# BMS.net
KiCad netlist of a schematic drawn in EAGLE
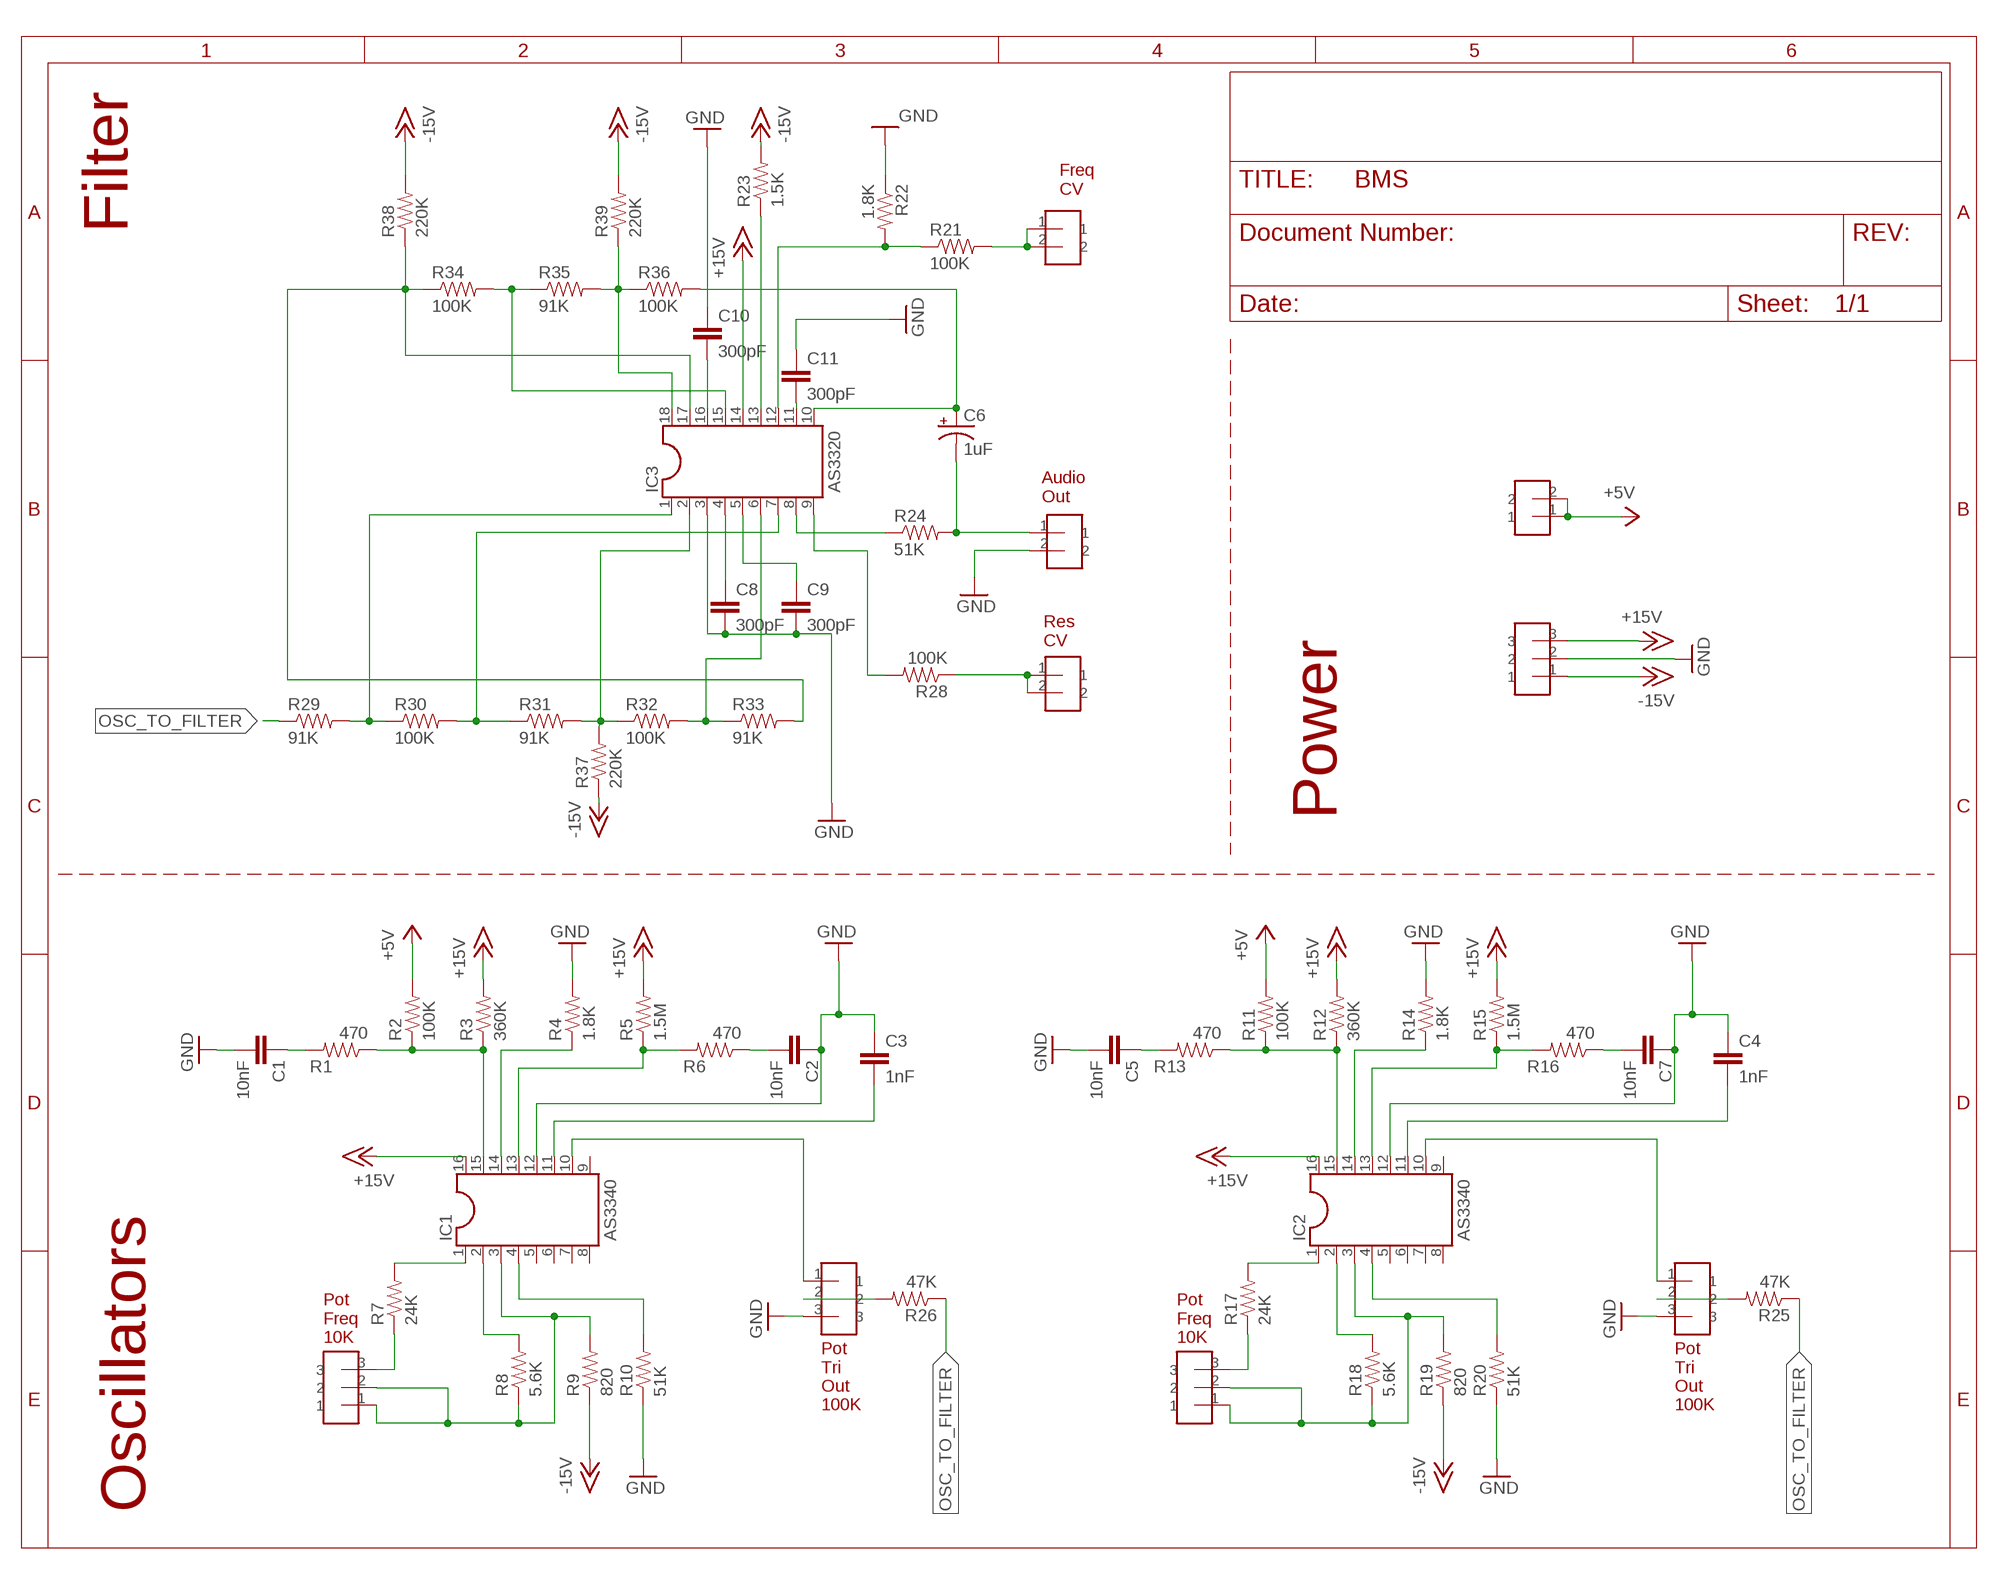
[diagram p0: schematic, sheet 1]

(export (version "E")
  (design (tool "Eeschema 10.0.6"))
  (components
    (comp (ref "C1")
      (value "10nF")
      (footprint "eagle-import:0805")
      (libsource (lib "eagle-import") (part "COMPONENT_CAP-0805"))
    )
    (comp (ref "C2")
      (value "10nF")
      (footprint "eagle-import:0805")
      (libsource (lib "eagle-import") (part "COMPONENT_CAP-0805"))
    )
    (comp (ref "C3")
      (value "1nF")
      (footprint "eagle-import:0805")
      (libsource (lib "eagle-import") (part "COMPONENT_CAP-0805"))
    )
    (comp (ref "C4")
      (value "1nF")
      (footprint "eagle-import:0805")
      (libsource (lib "eagle-import") (part "COMPONENT_CAP-0805"))
    )
    (comp (ref "C5")
      (value "10nF")
      (footprint "eagle-import:0805")
      (libsource (lib "eagle-import") (part "COMPONENT_CAP-0805"))
    )
    (comp (ref "C6")
      (value "1uF")
      (footprint "eagle-import:CAP_RADIAL_CAN_10MM")
      (libsource (lib "eagle-import") (part "COMPONENT_CAP_POL-6.3MM"))
    )
    (comp (ref "C7")
      (value "10nF")
      (footprint "eagle-import:0805")
      (libsource (lib "eagle-import") (part "COMPONENT_CAP-0805"))
    )
    (comp (ref "C8")
      (value "300pF")
      (footprint "eagle-import:0805")
      (libsource (lib "eagle-import") (part "COMPONENT_CAP-0805"))
    )
    (comp (ref "C9")
      (value "300pF")
      (footprint "eagle-import:0805")
      (libsource (lib "eagle-import") (part "COMPONENT_CAP-0805"))
    )
    (comp (ref "C10")
      (value "300pF")
      (footprint "eagle-import:0805")
      (libsource (lib "eagle-import") (part "COMPONENT_CAP-0805"))
    )
    (comp (ref "C11")
      (value "300pF")
      (footprint "eagle-import:0805")
      (libsource (lib "eagle-import") (part "COMPONENT_CAP-0805"))
    )
    (comp (ref "IC1")
      (value "AS3340")
      (footprint "eagle-import:SOCKET-16")
      (libsource (lib "eagle-import") (part "DIL16S"))
    )
    (comp (ref "IC2")
      (value "AS3340")
      (footprint "eagle-import:SOCKET-16")
      (libsource (lib "eagle-import") (part "DIL16S"))
    )
    (comp (ref "IC3")
      (value "AS3320")
      (footprint "eagle-import:SOCKET-18")
      (libsource (lib "eagle-import") (part "DIL18S"))
    )
    (comp (ref "R1")
      (value "470")
      (footprint "eagle-import:0805")
      (libsource (lib "eagle-import") (part "COMPONENT_RESISTOR-0805"))
    )
    (comp (ref "R2")
      (value "100K")
      (footprint "eagle-import:0805")
      (libsource (lib "eagle-import") (part "COMPONENT_RESISTOR-0805"))
    )
    (comp (ref "R3")
      (value "360K")
      (footprint "eagle-import:0805")
      (libsource (lib "eagle-import") (part "COMPONENT_RESISTOR-0805"))
    )
    (comp (ref "R4")
      (value "1.8K")
      (footprint "eagle-import:0805")
      (libsource (lib "eagle-import") (part "COMPONENT_RESISTOR-0805"))
    )
    (comp (ref "R5")
      (value "1.5M")
      (footprint "eagle-import:0805")
      (libsource (lib "eagle-import") (part "COMPONENT_RESISTOR-0805"))
    )
    (comp (ref "R6")
      (value "470")
      (footprint "eagle-import:0805")
      (libsource (lib "eagle-import") (part "COMPONENT_RESISTOR-0805"))
    )
    (comp (ref "R7")
      (value "24K")
      (footprint "eagle-import:0805")
      (libsource (lib "eagle-import") (part "COMPONENT_RESISTOR-0805"))
    )
    (comp (ref "R8")
      (value "5.6K")
      (footprint "eagle-import:0805")
      (libsource (lib "eagle-import") (part "COMPONENT_RESISTOR-0805"))
    )
    (comp (ref "R9")
      (value "820")
      (footprint "eagle-import:0805")
      (libsource (lib "eagle-import") (part "COMPONENT_RESISTOR-0805"))
    )
    (comp (ref "R10")
      (value "51K")
      (footprint "eagle-import:0805")
      (libsource (lib "eagle-import") (part "COMPONENT_RESISTOR-0805"))
    )
    (comp (ref "R11")
      (value "100K")
      (footprint "eagle-import:0805")
      (libsource (lib "eagle-import") (part "COMPONENT_RESISTOR-0805"))
    )
    (comp (ref "R12")
      (value "360K")
      (footprint "eagle-import:0805")
      (libsource (lib "eagle-import") (part "COMPONENT_RESISTOR-0805"))
    )
    (comp (ref "R13")
      (value "470")
      (footprint "eagle-import:0805")
      (libsource (lib "eagle-import") (part "COMPONENT_RESISTOR-0805"))
    )
    (comp (ref "R14")
      (value "1.8K")
      (footprint "eagle-import:0805")
      (libsource (lib "eagle-import") (part "COMPONENT_RESISTOR-0805"))
    )
    (comp (ref "R15")
      (value "1.5M")
      (footprint "eagle-import:0805")
      (libsource (lib "eagle-import") (part "COMPONENT_RESISTOR-0805"))
    )
    (comp (ref "R16")
      (value "470")
      (footprint "eagle-import:0805")
      (libsource (lib "eagle-import") (part "COMPONENT_RESISTOR-0805"))
    )
    (comp (ref "R17")
      (value "24K")
      (footprint "eagle-import:0805")
      (libsource (lib "eagle-import") (part "COMPONENT_RESISTOR-0805"))
    )
    (comp (ref "R18")
      (value "5.6K")
      (footprint "eagle-import:0805")
      (libsource (lib "eagle-import") (part "COMPONENT_RESISTOR-0805"))
    )
    (comp (ref "R19")
      (value "820")
      (footprint "eagle-import:0805")
      (libsource (lib "eagle-import") (part "COMPONENT_RESISTOR-0805"))
    )
    (comp (ref "R20")
      (value "51K")
      (footprint "eagle-import:0805")
      (libsource (lib "eagle-import") (part "COMPONENT_RESISTOR-0805"))
    )
    (comp (ref "R21")
      (value "100K")
      (footprint "eagle-import:0805")
      (libsource (lib "eagle-import") (part "COMPONENT_RESISTOR-0805"))
    )
    (comp (ref "R22")
      (value "1.8K")
      (footprint "eagle-import:0805")
      (libsource (lib "eagle-import") (part "COMPONENT_RESISTOR-0805"))
    )
    (comp (ref "R23")
      (value "1.5K")
      (footprint "eagle-import:0805")
      (libsource (lib "eagle-import") (part "COMPONENT_RESISTOR-0805"))
    )
    (comp (ref "R24")
      (value "51K")
      (footprint "eagle-import:0805")
      (libsource (lib "eagle-import") (part "COMPONENT_RESISTOR-0805"))
    )
    (comp (ref "R25")
      (value "47K")
      (footprint "eagle-import:0805")
      (libsource (lib "eagle-import") (part "COMPONENT_RESISTOR-0805"))
    )
    (comp (ref "R26")
      (value "47K")
      (footprint "eagle-import:0805")
      (libsource (lib "eagle-import") (part "COMPONENT_RESISTOR-0805"))
    )
    (comp (ref "R28")
      (value "100K")
      (footprint "eagle-import:0805")
      (libsource (lib "eagle-import") (part "COMPONENT_RESISTOR-0805"))
    )
    (comp (ref "R29")
      (value "91K")
      (footprint "eagle-import:0805")
      (libsource (lib "eagle-import") (part "COMPONENT_RESISTOR-0805"))
    )
    (comp (ref "R30")
      (value "100K")
      (footprint "eagle-import:0805")
      (libsource (lib "eagle-import") (part "COMPONENT_RESISTOR-0805"))
    )
    (comp (ref "R31")
      (value "91K")
      (footprint "eagle-import:0805")
      (libsource (lib "eagle-import") (part "COMPONENT_RESISTOR-0805"))
    )
    (comp (ref "R32")
      (value "100K")
      (footprint "eagle-import:0805")
      (libsource (lib "eagle-import") (part "COMPONENT_RESISTOR-0805"))
    )
    (comp (ref "R33")
      (value "91K")
      (footprint "eagle-import:0805")
      (libsource (lib "eagle-import") (part "COMPONENT_RESISTOR-0805"))
    )
    (comp (ref "R34")
      (value "100K")
      (footprint "eagle-import:0805")
      (libsource (lib "eagle-import") (part "COMPONENT_RESISTOR-0805"))
    )
    (comp (ref "R35")
      (value "91K")
      (footprint "eagle-import:0805")
      (libsource (lib "eagle-import") (part "COMPONENT_RESISTOR-0805"))
    )
    (comp (ref "R36")
      (value "100K")
      (footprint "eagle-import:0805")
      (libsource (lib "eagle-import") (part "COMPONENT_RESISTOR-0805"))
    )
    (comp (ref "R37")
      (value "220K")
      (footprint "eagle-import:0805")
      (libsource (lib "eagle-import") (part "COMPONENT_RESISTOR-0805"))
    )
    (comp (ref "R38")
      (value "220K")
      (footprint "eagle-import:0805")
      (libsource (lib "eagle-import") (part "COMPONENT_RESISTOR-0805"))
    )
    (comp (ref "R39")
      (value "220K")
      (footprint "eagle-import:0805")
      (libsource (lib "eagle-import") (part "COMPONENT_RESISTOR-0805"))
    )
    (comp (ref "U$1")
      (value "HEADER-3-VERTICAL")
      (footprint "eagle-import:HEADER-3-VERTICAL")
      (libsource (lib "eagle-import") (part "HEADER-3-VERTICAL"))
    )
    (comp (ref "U$2")
      (value "HEADER-2-VERTICAL")
      (footprint "eagle-import:HEADER-2-VERTICAL")
      (libsource (lib "eagle-import") (part "HEADER-2-VERTICAL"))
    )
    (comp (ref "U$3")
      (value "HEADER-2-VERTICAL")
      (footprint "eagle-import:HEADER-2-VERTICAL")
      (libsource (lib "eagle-import") (part "HEADER-2-VERTICAL"))
    )
    (comp (ref "U$4")
      (value "HEADER-3-VERTICAL")
      (footprint "eagle-import:HEADER-3-VERTICAL")
      (libsource (lib "eagle-import") (part "HEADER-3-VERTICAL"))
    )
    (comp (ref "U$6")
      (value "HEADER-3-VERTICAL")
      (footprint "eagle-import:HEADER-3-VERTICAL")
      (libsource (lib "eagle-import") (part "HEADER-3-VERTICAL"))
    )
    (comp (ref "U$8")
      (value "HEADER-3-VERTICAL")
      (footprint "eagle-import:HEADER-3-VERTICAL")
      (libsource (lib "eagle-import") (part "HEADER-3-VERTICAL"))
    )
    (comp (ref "U$10")
      (value "HEADER-3-VERTICAL")
      (footprint "eagle-import:HEADER-3-VERTICAL")
      (libsource (lib "eagle-import") (part "HEADER-3-VERTICAL"))
    )
    (comp (ref "U$13")
      (value "HEADER-2-VERTICAL")
      (footprint "eagle-import:HEADER-2-VERTICAL")
      (libsource (lib "eagle-import") (part "HEADER-2-VERTICAL"))
    )
    (comp (ref "U$14")
      (value "HEADER-2-VERTICAL")
      (footprint "eagle-import:HEADER-2-VERTICAL")
      (libsource (lib "eagle-import") (part "HEADER-2-VERTICAL"))
    )
  )
  (nets
    (net (code "1") (name "+5V") (class "Default")
      (node (ref "R11") (pin "2") (pinfunction "2_2") (pintype "passive"))
      (node (ref "R2") (pin "2") (pinfunction "2_2") (pintype "passive"))
      (node (ref "U$3") (pin "1") (pinfunction "1_1") (pintype "bidirectional"))
      (node (ref "U$3") (pin "2") (pinfunction "2_2") (pintype "bidirectional"))
    )
    (net (code "2") (name "+15V") (class "Default")
      (node (ref "IC1") (pin "16") (pinfunction "16_16") (pintype "passive"))
      (node (ref "IC2") (pin "16") (pinfunction "16_16") (pintype "passive"))
      (node (ref "IC3") (pin "14") (pinfunction "14_14") (pintype "passive"))
      (node (ref "R12") (pin "2") (pinfunction "2_2") (pintype "passive"))
      (node (ref "R15") (pin "2") (pinfunction "2_2") (pintype "passive"))
      (node (ref "R3") (pin "2") (pinfunction "2_2") (pintype "passive"))
      (node (ref "R5") (pin "2") (pinfunction "2_2") (pintype "passive"))
      (node (ref "U$6") (pin "3") (pinfunction "3_3") (pintype "bidirectional"))
    )
    (net (code "3") (name "-15V") (class "Default")
      (node (ref "R19") (pin "1") (pinfunction "1_1") (pintype "passive"))
      (node (ref "R23") (pin "2") (pinfunction "2_2") (pintype "passive"))
      (node (ref "R37") (pin "1") (pinfunction "1_1") (pintype "passive"))
      (node (ref "R38") (pin "2") (pinfunction "2_2") (pintype "passive"))
      (node (ref "R39") (pin "2") (pinfunction "2_2") (pintype "passive"))
      (node (ref "R9") (pin "1") (pinfunction "1_1") (pintype "passive"))
      (node (ref "U$6") (pin "1") (pinfunction "1_1") (pintype "bidirectional"))
    )
    (net (code "4") (name "GND") (class "Default")
      (node (ref "C1") (pin "2") (pinfunction "2_2") (pintype "passive"))
      (node (ref "C10") (pin "1") (pinfunction "1_1") (pintype "passive"))
      (node (ref "C11") (pin "1") (pinfunction "1_1") (pintype "passive"))
      (node (ref "C2") (pin "1") (pinfunction "1_1") (pintype "passive"))
      (node (ref "C3") (pin "1") (pinfunction "1_1") (pintype "passive"))
      (node (ref "C4") (pin "1") (pinfunction "1_1") (pintype "passive"))
      (node (ref "C5") (pin "2") (pinfunction "2_2") (pintype "passive"))
      (node (ref "C7") (pin "1") (pinfunction "1_1") (pintype "passive"))
      (node (ref "C8") (pin "2") (pinfunction "2_2") (pintype "passive"))
      (node (ref "C9") (pin "2") (pinfunction "2_2") (pintype "passive"))
      (node (ref "IC1") (pin "12") (pinfunction "12_12") (pintype "passive"))
      (node (ref "IC2") (pin "12") (pinfunction "12_12") (pintype "passive"))
      (node (ref "IC3") (pin "3") (pinfunction "3_3") (pintype "passive"))
      (node (ref "R10") (pin "1") (pinfunction "1_1") (pintype "passive"))
      (node (ref "R14") (pin "2") (pinfunction "2_2") (pintype "passive"))
      (node (ref "R20") (pin "1") (pinfunction "1_1") (pintype "passive"))
      (node (ref "R22") (pin "1") (pinfunction "1_1") (pintype "passive"))
      (node (ref "R4") (pin "2") (pinfunction "2_2") (pintype "passive"))
      (node (ref "U$10") (pin "3") (pinfunction "3_3") (pintype "bidirectional"))
      (node (ref "U$14") (pin "2") (pinfunction "2_2") (pintype "bidirectional"))
      (node (ref "U$4") (pin "3") (pinfunction "3_3") (pintype "bidirectional"))
      (node (ref "U$6") (pin "2") (pinfunction "2_2") (pintype "bidirectional"))
    )
    (net (code "5") (name "Net-(C1-Pad1)") (class "Default")
      (node (ref "C1") (pin "1") (pinfunction "1_1") (pintype "passive"))
      (node (ref "R1") (pin "2") (pinfunction "2_2") (pintype "passive"))
    )
    (net (code "6") (name "Net-(C2-Pad2)") (class "Default")
      (node (ref "C2") (pin "2") (pinfunction "2_2") (pintype "passive"))
      (node (ref "R6") (pin "1") (pinfunction "1_1") (pintype "passive"))
    )
    (net (code "7") (name "Net-(C3-Pad2)") (class "Default")
      (node (ref "C3") (pin "2") (pinfunction "2_2") (pintype "passive"))
      (node (ref "IC1") (pin "11") (pinfunction "11_11") (pintype "passive"))
    )
    (net (code "8") (name "Net-(C4-Pad2)") (class "Default")
      (node (ref "C4") (pin "2") (pinfunction "2_2") (pintype "passive"))
      (node (ref "IC2") (pin "11") (pinfunction "11_11") (pintype "passive"))
    )
    (net (code "9") (name "Net-(C5-Pad1)") (class "Default")
      (node (ref "C5") (pin "1") (pinfunction "1_1") (pintype "passive"))
      (node (ref "R13") (pin "2") (pinfunction "2_2") (pintype "passive"))
    )
    (net (code "10") (name "Net-(C6-Pad+)") (class "Default")
      (node (ref "C6") (pin "+") (pinfunction "+_+") (pintype "passive"))
      (node (ref "IC3") (pin "10") (pinfunction "10_10") (pintype "passive"))
      (node (ref "R36") (pin "2") (pinfunction "2_2") (pintype "passive"))
    )
    (net (code "11") (name "Net-(C6-Pad-)") (class "Default")
      (node (ref "C6") (pin "-") (pinfunction "-_-") (pintype "passive"))
      (node (ref "R24") (pin "2") (pinfunction "2_2") (pintype "passive"))
      (node (ref "U$14") (pin "1") (pinfunction "1_1") (pintype "bidirectional"))
    )
    (net (code "12") (name "Net-(C7-Pad2)") (class "Default")
      (node (ref "C7") (pin "2") (pinfunction "2_2") (pintype "passive"))
      (node (ref "R16") (pin "1") (pinfunction "1_1") (pintype "passive"))
    )
    (net (code "13") (name "Net-(C8-Pad1)") (class "Default")
      (node (ref "C8") (pin "1") (pinfunction "1_1") (pintype "passive"))
      (node (ref "IC3") (pin "4") (pinfunction "4_4") (pintype "passive"))
    )
    (net (code "14") (name "Net-(C9-Pad1)") (class "Default")
      (node (ref "C9") (pin "1") (pinfunction "1_1") (pintype "passive"))
      (node (ref "IC3") (pin "5") (pinfunction "5_5") (pintype "passive"))
    )
    (net (code "15") (name "Net-(C10-Pad2)") (class "Default")
      (node (ref "C10") (pin "2") (pinfunction "2_2") (pintype "passive"))
      (node (ref "IC3") (pin "16") (pinfunction "16_16") (pintype "passive"))
    )
    (net (code "16") (name "Net-(C11-Pad2)") (class "Default")
      (node (ref "C11") (pin "2") (pinfunction "2_2") (pintype "passive"))
      (node (ref "IC3") (pin "11") (pinfunction "11_11") (pintype "passive"))
    )
    (net (code "17") (name "Net-(IC1-Pad1)") (class "Default")
      (node (ref "IC1") (pin "1") (pinfunction "1_1") (pintype "passive"))
      (node (ref "R7") (pin "2") (pinfunction "2_2") (pintype "passive"))
    )
    (net (code "18") (name "Net-(IC1-Pad2)") (class "Default")
      (node (ref "IC1") (pin "2") (pinfunction "2_2") (pintype "passive"))
      (node (ref "R8") (pin "2") (pinfunction "2_2") (pintype "passive"))
    )
    (net (code "19") (name "Net-(IC1-Pad3)") (class "Default")
      (node (ref "IC1") (pin "3") (pinfunction "3_3") (pintype "passive"))
      (node (ref "R8") (pin "1") (pinfunction "1_1") (pintype "passive"))
      (node (ref "R9") (pin "2") (pinfunction "2_2") (pintype "passive"))
      (node (ref "U$1") (pin "1") (pinfunction "1_1") (pintype "bidirectional"))
      (node (ref "U$1") (pin "2") (pinfunction "2_2") (pintype "bidirectional"))
    )
    (net (code "20") (name "Net-(IC1-Pad4)") (class "Default")
      (node (ref "IC1") (pin "4") (pinfunction "4_4") (pintype "passive"))
      (node (ref "R10") (pin "2") (pinfunction "2_2") (pintype "passive"))
    )
    (net (code "21") (name "Net-(IC1-Pad10)") (class "Default")
      (node (ref "IC1") (pin "10") (pinfunction "10_10") (pintype "passive"))
      (node (ref "U$4") (pin "1") (pinfunction "1_1") (pintype "bidirectional"))
    )
    (net (code "22") (name "Net-(IC1-Pad13)") (class "Default")
      (node (ref "IC1") (pin "13") (pinfunction "13_13") (pintype "passive"))
      (node (ref "R5") (pin "1") (pinfunction "1_1") (pintype "passive"))
      (node (ref "R6") (pin "2") (pinfunction "2_2") (pintype "passive"))
    )
    (net (code "23") (name "Net-(IC1-Pad14)") (class "Default")
      (node (ref "IC1") (pin "14") (pinfunction "14_14") (pintype "passive"))
      (node (ref "R4") (pin "1") (pinfunction "1_1") (pintype "passive"))
    )
    (net (code "24") (name "Net-(IC1-Pad15)") (class "Default")
      (node (ref "IC1") (pin "15") (pinfunction "15_15") (pintype "passive"))
      (node (ref "R1") (pin "1") (pinfunction "1_1") (pintype "passive"))
      (node (ref "R2") (pin "1") (pinfunction "1_1") (pintype "passive"))
      (node (ref "R3") (pin "1") (pinfunction "1_1") (pintype "passive"))
    )
    (net (code "25") (name "Net-(IC2-Pad1)") (class "Default")
      (node (ref "IC2") (pin "1") (pinfunction "1_1") (pintype "passive"))
      (node (ref "R17") (pin "2") (pinfunction "2_2") (pintype "passive"))
    )
    (net (code "26") (name "Net-(IC2-Pad2)") (class "Default")
      (node (ref "IC2") (pin "2") (pinfunction "2_2") (pintype "passive"))
      (node (ref "R18") (pin "2") (pinfunction "2_2") (pintype "passive"))
    )
    (net (code "27") (name "Net-(IC2-Pad3)") (class "Default")
      (node (ref "IC2") (pin "3") (pinfunction "3_3") (pintype "passive"))
      (node (ref "R18") (pin "1") (pinfunction "1_1") (pintype "passive"))
      (node (ref "R19") (pin "2") (pinfunction "2_2") (pintype "passive"))
      (node (ref "U$8") (pin "1") (pinfunction "1_1") (pintype "bidirectional"))
      (node (ref "U$8") (pin "2") (pinfunction "2_2") (pintype "bidirectional"))
    )
    (net (code "28") (name "Net-(IC2-Pad4)") (class "Default")
      (node (ref "IC2") (pin "4") (pinfunction "4_4") (pintype "passive"))
      (node (ref "R20") (pin "2") (pinfunction "2_2") (pintype "passive"))
    )
    (net (code "29") (name "Net-(IC2-Pad10)") (class "Default")
      (node (ref "IC2") (pin "10") (pinfunction "10_10") (pintype "passive"))
      (node (ref "U$10") (pin "1") (pinfunction "1_1") (pintype "bidirectional"))
    )
    (net (code "30") (name "Net-(IC2-Pad13)") (class "Default")
      (node (ref "IC2") (pin "13") (pinfunction "13_13") (pintype "passive"))
      (node (ref "R15") (pin "1") (pinfunction "1_1") (pintype "passive"))
      (node (ref "R16") (pin "2") (pinfunction "2_2") (pintype "passive"))
    )
    (net (code "31") (name "Net-(IC2-Pad14)") (class "Default")
      (node (ref "IC2") (pin "14") (pinfunction "14_14") (pintype "passive"))
      (node (ref "R14") (pin "1") (pinfunction "1_1") (pintype "passive"))
    )
    (net (code "32") (name "Net-(IC2-Pad15)") (class "Default")
      (node (ref "IC2") (pin "15") (pinfunction "15_15") (pintype "passive"))
      (node (ref "R11") (pin "1") (pinfunction "1_1") (pintype "passive"))
      (node (ref "R12") (pin "1") (pinfunction "1_1") (pintype "passive"))
      (node (ref "R13") (pin "1") (pinfunction "1_1") (pintype "passive"))
    )
    (net (code "33") (name "Net-(IC3-Pad1)") (class "Default")
      (node (ref "IC3") (pin "1") (pinfunction "1_1") (pintype "passive"))
      (node (ref "R29") (pin "2") (pinfunction "2_2") (pintype "passive"))
      (node (ref "R30") (pin "1") (pinfunction "1_1") (pintype "passive"))
    )
    (net (code "34") (name "Net-(IC3-Pad2)") (class "Default")
      (node (ref "IC3") (pin "2") (pinfunction "2_2") (pintype "passive"))
      (node (ref "R31") (pin "2") (pinfunction "2_2") (pintype "passive"))
      (node (ref "R32") (pin "1") (pinfunction "1_1") (pintype "passive"))
      (node (ref "R37") (pin "2") (pinfunction "2_2") (pintype "passive"))
    )
    (net (code "35") (name "Net-(IC3-Pad6)") (class "Default")
      (node (ref "IC3") (pin "6") (pinfunction "6_6") (pintype "passive"))
      (node (ref "R32") (pin "2") (pinfunction "2_2") (pintype "passive"))
      (node (ref "R33") (pin "1") (pinfunction "1_1") (pintype "passive"))
    )
    (net (code "36") (name "Net-(IC3-Pad7)") (class "Default")
      (node (ref "IC3") (pin "7") (pinfunction "7_7") (pintype "passive"))
      (node (ref "R30") (pin "2") (pinfunction "2_2") (pintype "passive"))
      (node (ref "R31") (pin "1") (pinfunction "1_1") (pintype "passive"))
    )
    (net (code "37") (name "Net-(IC3-Pad8)") (class "Default")
      (node (ref "IC3") (pin "8") (pinfunction "8_8") (pintype "passive"))
      (node (ref "R24") (pin "1") (pinfunction "1_1") (pintype "passive"))
    )
    (net (code "38") (name "Net-(IC3-Pad9)") (class "Default")
      (node (ref "IC3") (pin "9") (pinfunction "9_9") (pintype "passive"))
      (node (ref "R28") (pin "2") (pinfunction "2_2") (pintype "passive"))
    )
    (net (code "39") (name "Net-(IC3-Pad12)") (class "Default")
      (node (ref "IC3") (pin "12") (pinfunction "12_12") (pintype "passive"))
      (node (ref "R21") (pin "1") (pinfunction "1_1") (pintype "passive"))
      (node (ref "R22") (pin "2") (pinfunction "2_2") (pintype "passive"))
    )
    (net (code "40") (name "Net-(IC3-Pad13)") (class "Default")
      (node (ref "IC3") (pin "13") (pinfunction "13_13") (pintype "passive"))
      (node (ref "R23") (pin "1") (pinfunction "1_1") (pintype "passive"))
    )
    (net (code "41") (name "Net-(IC3-Pad15)") (class "Default")
      (node (ref "IC3") (pin "15") (pinfunction "15_15") (pintype "passive"))
      (node (ref "R34") (pin "2") (pinfunction "2_2") (pintype "passive"))
      (node (ref "R35") (pin "1") (pinfunction "1_1") (pintype "passive"))
    )
    (net (code "42") (name "Net-(IC3-Pad17)") (class "Default")
      (node (ref "IC3") (pin "17") (pinfunction "17_17") (pintype "passive"))
      (node (ref "R33") (pin "2") (pinfunction "2_2") (pintype "passive"))
      (node (ref "R34") (pin "1") (pinfunction "1_1") (pintype "passive"))
      (node (ref "R38") (pin "1") (pinfunction "1_1") (pintype "passive"))
    )
    (net (code "43") (name "Net-(IC3-Pad18)") (class "Default")
      (node (ref "IC3") (pin "18") (pinfunction "18_18") (pintype "passive"))
      (node (ref "R35") (pin "2") (pinfunction "2_2") (pintype "passive"))
      (node (ref "R36") (pin "1") (pinfunction "1_1") (pintype "passive"))
      (node (ref "R39") (pin "1") (pinfunction "1_1") (pintype "passive"))
    )
    (net (code "44") (name "Net-(R7-Pad1)") (class "Default")
      (node (ref "R7") (pin "1") (pinfunction "1_1") (pintype "passive"))
      (node (ref "U$1") (pin "3") (pinfunction "3_3") (pintype "bidirectional"))
    )
    (net (code "45") (name "Net-(R17-Pad1)") (class "Default")
      (node (ref "R17") (pin "1") (pinfunction "1_1") (pintype "passive"))
      (node (ref "U$8") (pin "3") (pinfunction "3_3") (pintype "bidirectional"))
    )
    (net (code "46") (name "Net-(R21-Pad2)") (class "Default")
      (node (ref "R21") (pin "2") (pinfunction "2_2") (pintype "passive"))
      (node (ref "U$2") (pin "1") (pinfunction "1_1") (pintype "bidirectional"))
      (node (ref "U$2") (pin "2") (pinfunction "2_2") (pintype "bidirectional"))
    )
    (net (code "47") (name "Net-(R25-Pad2)") (class "Default")
      (node (ref "R25") (pin "2") (pinfunction "2_2") (pintype "passive"))
      (node (ref "U$10") (pin "2") (pinfunction "2_2") (pintype "bidirectional"))
    )
    (net (code "48") (name "Net-(R26-Pad2)") (class "Default")
      (node (ref "R26") (pin "2") (pinfunction "2_2") (pintype "passive"))
      (node (ref "U$4") (pin "2") (pinfunction "2_2") (pintype "bidirectional"))
    )
    (net (code "49") (name "Net-(R28-Pad1)") (class "Default")
      (node (ref "R28") (pin "1") (pinfunction "1_1") (pintype "passive"))
      (node (ref "U$13") (pin "1") (pinfunction "1_1") (pintype "bidirectional"))
      (node (ref "U$13") (pin "2") (pinfunction "2_2") (pintype "bidirectional"))
    )
    (net (code "50") (name "OSC_TO_FILTER") (class "Default")
      (node (ref "R25") (pin "1") (pinfunction "1_1") (pintype "passive"))
      (node (ref "R26") (pin "1") (pinfunction "1_1") (pintype "passive"))
      (node (ref "R29") (pin "1") (pinfunction "1_1") (pintype "passive"))
    )
    (net (code "51") (name "unconnected-(IC1-Pad5)") (class "Default")
      (node (ref "IC1") (pin "5") (pinfunction "5_5") (pintype "passive"))
    )
    (net (code "52") (name "unconnected-(IC1-Pad6)") (class "Default")
      (node (ref "IC1") (pin "6") (pinfunction "6_6") (pintype "passive"))
    )
    (net (code "53") (name "unconnected-(IC1-Pad7)") (class "Default")
      (node (ref "IC1") (pin "7") (pinfunction "7_7") (pintype "passive"))
    )
    (net (code "54") (name "unconnected-(IC1-Pad8)") (class "Default")
      (node (ref "IC1") (pin "8") (pinfunction "8_8") (pintype "passive"))
    )
    (net (code "55") (name "unconnected-(IC1-Pad9)") (class "Default")
      (node (ref "IC1") (pin "9") (pinfunction "9_9") (pintype "passive"))
    )
    (net (code "56") (name "unconnected-(IC2-Pad5)") (class "Default")
      (node (ref "IC2") (pin "5") (pinfunction "5_5") (pintype "passive"))
    )
    (net (code "57") (name "unconnected-(IC2-Pad6)") (class "Default")
      (node (ref "IC2") (pin "6") (pinfunction "6_6") (pintype "passive"))
    )
    (net (code "58") (name "unconnected-(IC2-Pad7)") (class "Default")
      (node (ref "IC2") (pin "7") (pinfunction "7_7") (pintype "passive"))
    )
    (net (code "59") (name "unconnected-(IC2-Pad8)") (class "Default")
      (node (ref "IC2") (pin "8") (pinfunction "8_8") (pintype "passive"))
    )
    (net (code "60") (name "unconnected-(IC2-Pad9)") (class "Default")
      (node (ref "IC2") (pin "9") (pinfunction "9_9") (pintype "passive"))
    )
  )
)
